# SCH_semi-automatic-healing-reminder_2026.net
KiCad netlist of a schematic drawn in EasyEDA
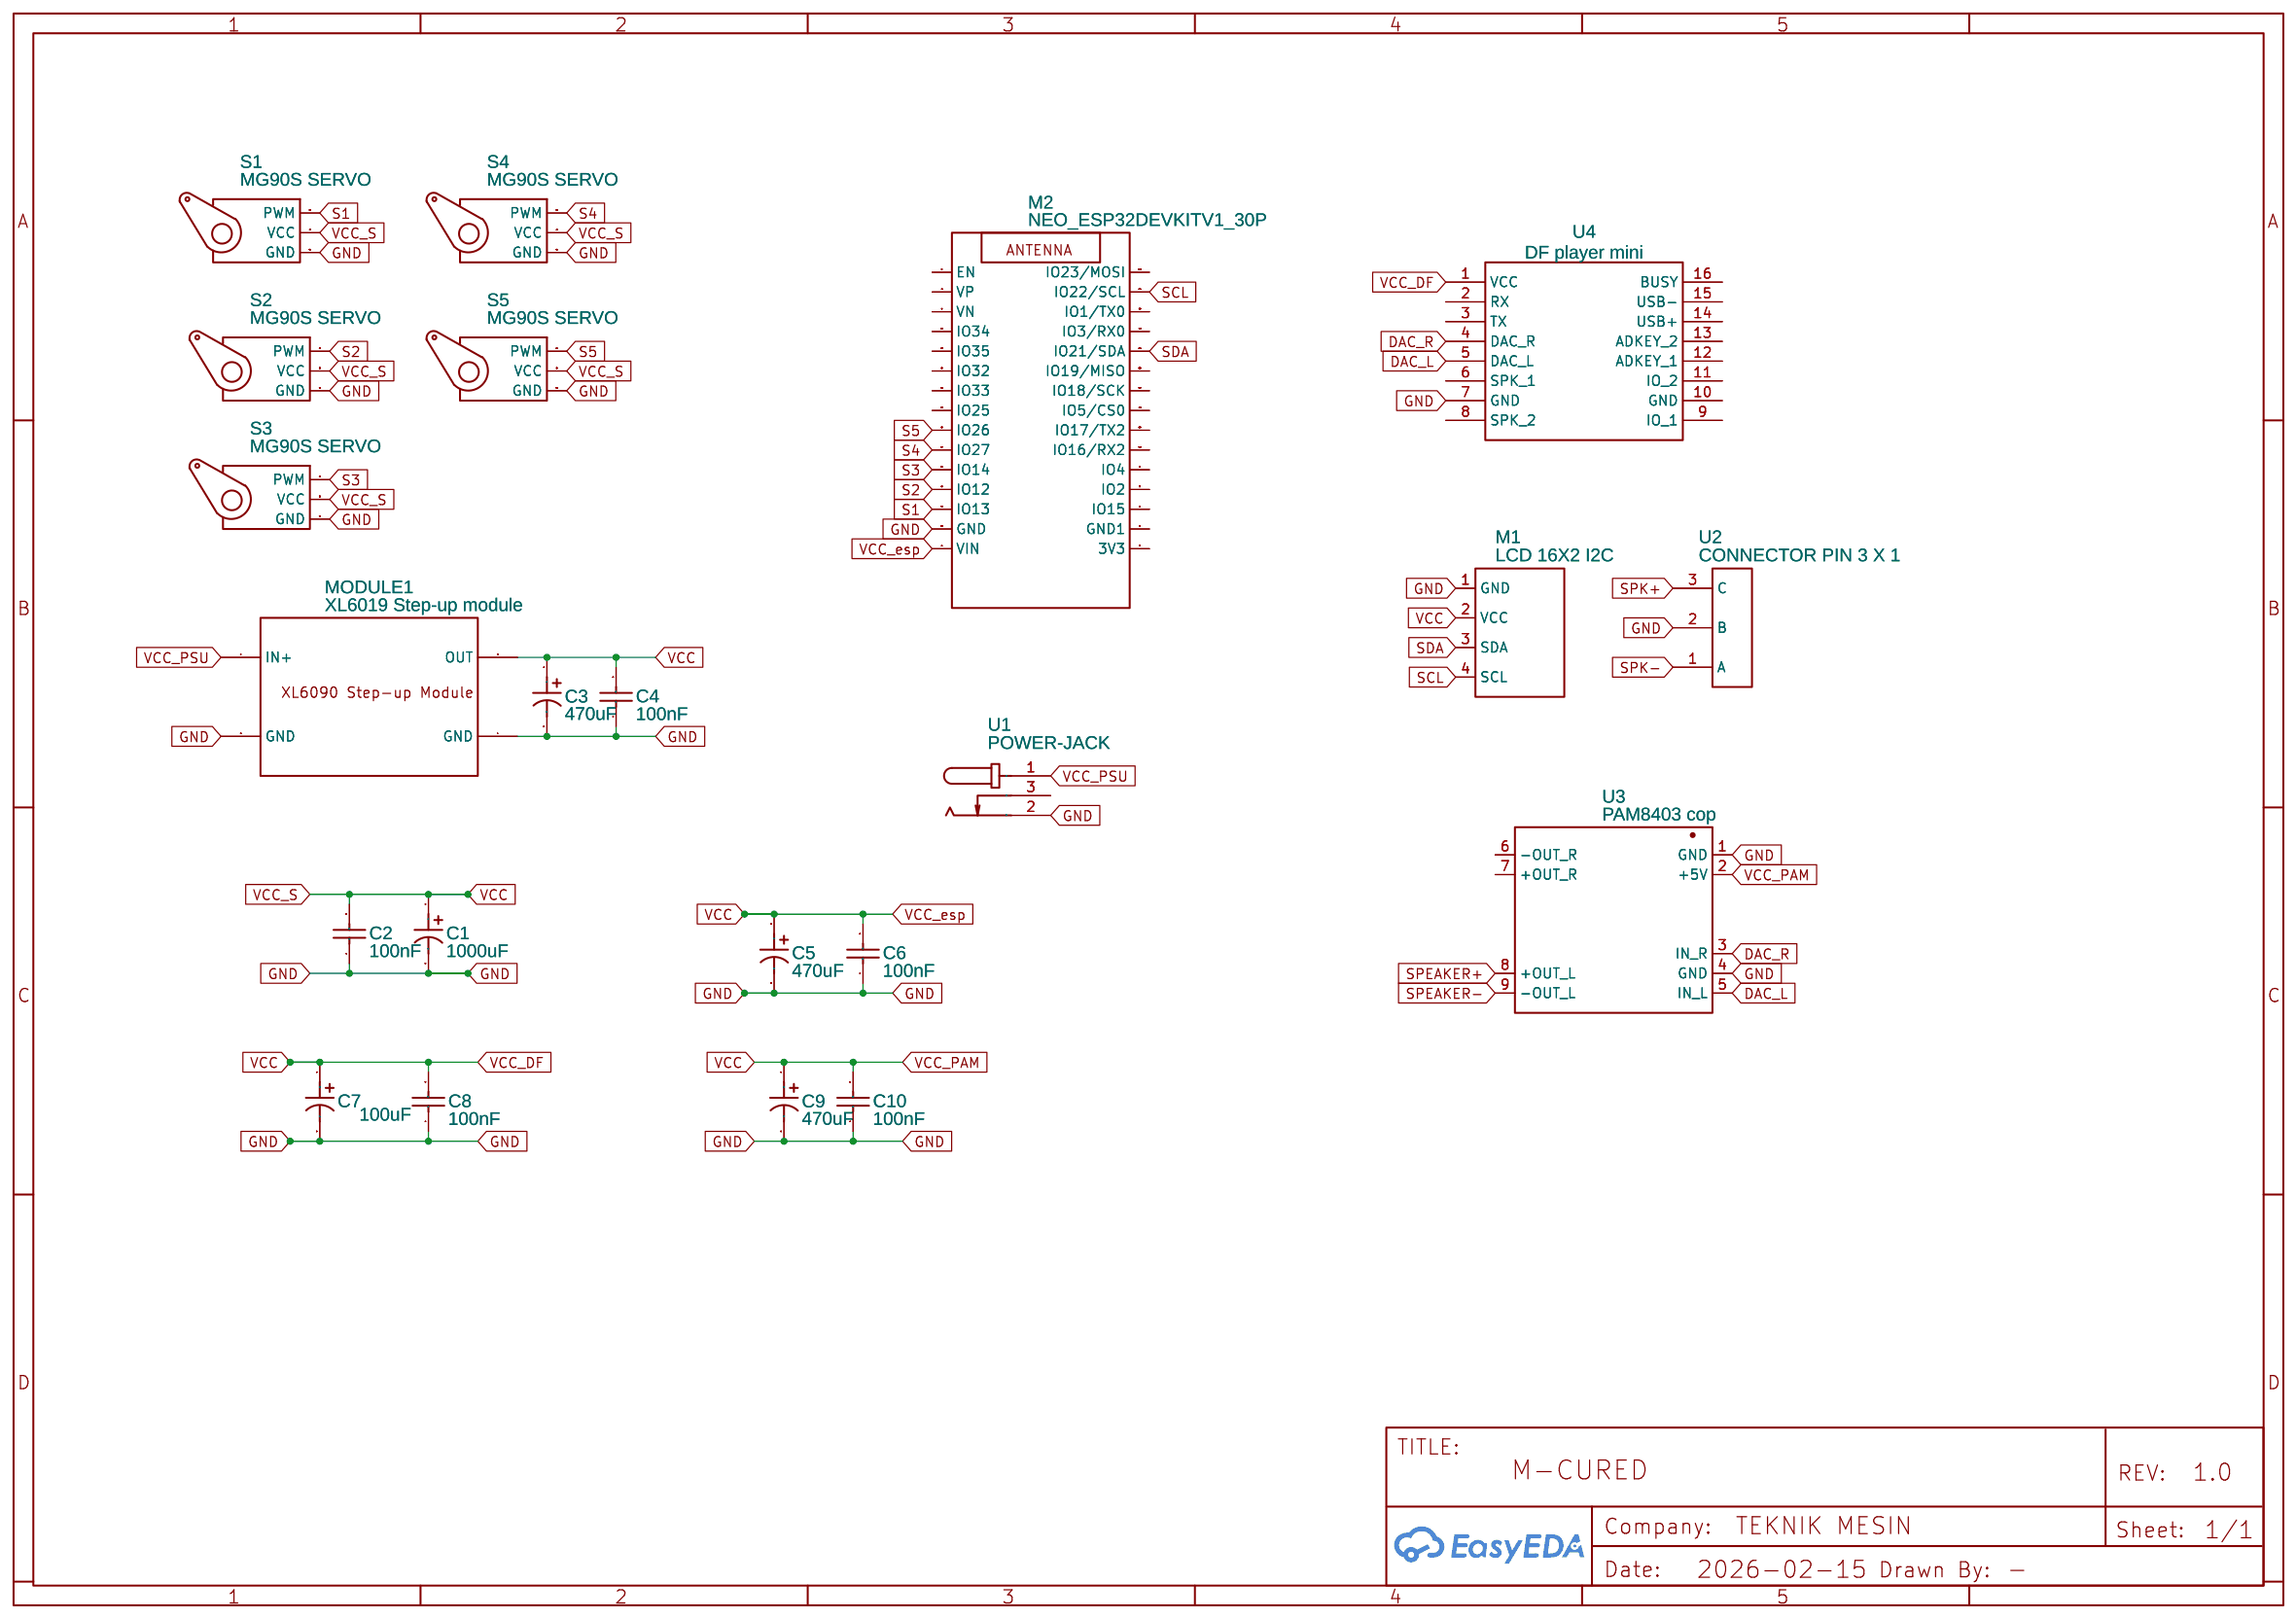
[diagram p0: schematic sheet]

(export (version "E")
  (design (tool "Eeschema 10.0.6"))
  (components
    (comp (ref "C1")
      (value "1000uF")
      (fields
        (field (name "Manufacturer Part") "1000uF10V8x14GF")
        (field (name "Manufacturer") "Econd(米朗电子)")
      )
      (libsource (lib "") (part "1000UF10V8X14GF"))
    )
    (comp (ref "C2")
      (value "100nF")
      (fields
        (field (name "Manufacturer Part") "100nF (104) ±20% 100V")
        (field (name "Manufacturer") "ReliaPro")
      )
      (libsource (lib "") (part "100nF"))
    )
    (comp (ref "C3")
      (value "470uF")
      (fields (field (name "Manufacturer Part") "470UF25VF140KM") (field (name "Manufacturer") "Econd(米朗电子)"))
      (libsource (lib "") (part "470UF25VF140KM"))
    )
    (comp (ref "C4")
      (value "100nF")
      (fields
        (field (name "Manufacturer Part") "100nF (104) ±20% 100V")
        (field (name "Manufacturer") "ReliaPro")
      )
      (libsource (lib "") (part "100nF"))
    )
    (comp (ref "C5")
      (value "470uF")
      (fields (field (name "Manufacturer Part") "470UF25VF140KM") (field (name "Manufacturer") "Econd(米朗电子)"))
      (libsource (lib "") (part "470UF25VF140KM"))
    )
    (comp (ref "C6")
      (value "100nF")
      (fields
        (field (name "Manufacturer Part") "100nF (104) ±20% 100V")
        (field (name "Manufacturer") "ReliaPro")
      )
      (libsource (lib "") (part "100nF"))
    )
    (comp (ref "C7")
      (value "100uF")
      (fields
        (field (name "Manufacturer Part") "100uF25V6.3x11KM")
        (field (name "Manufacturer") "Econd(米朗电子)")
      )
      (libsource (lib "") (part "100UF25V6.3X11KM"))
    )
    (comp (ref "C8")
      (value "100nF")
      (fields
        (field (name "Manufacturer Part") "100nF (104) ±20% 100V")
        (field (name "Manufacturer") "ReliaPro")
      )
      (libsource (lib "") (part "100nF"))
    )
    (comp (ref "C9")
      (value "470uF")
      (fields (field (name "Manufacturer Part") "470UF25VF140KM") (field (name "Manufacturer") "Econd(米朗电子)"))
      (libsource (lib "") (part "470UF25VF140KM"))
    )
    (comp (ref "C10")
      (value "100nF")
      (fields
        (field (name "Manufacturer Part") "100nF (104) ±20% 100V")
        (field (name "Manufacturer") "ReliaPro")
      )
      (libsource (lib "") (part "100nF"))
    )
    (comp (ref "M1") (value "LCD 16X2 I2C") (libsource (lib "") (part "LCD 16X2 I2C")))
    (comp (ref "M2") (value "NEO_ESP32DEVKITV1_30P") (libsource (lib "") (part "NEO_ESP32DEVKITV1_30P")))
    (comp (ref "MODULE1") (value "XL6019 Step-up module") (libsource (lib "") (part "XL6019 Step-up module")))
    (comp (ref "S1") (value "MG90S SERVO") (libsource (lib "") (part "MG90S SERVO")))
    (comp (ref "S2") (value "MG90S SERVO") (libsource (lib "") (part "MG90S SERVO")))
    (comp (ref "S3") (value "MG90S SERVO") (libsource (lib "") (part "MG90S SERVO")))
    (comp (ref "S4") (value "MG90S SERVO") (libsource (lib "") (part "MG90S SERVO")))
    (comp (ref "S5") (value "MG90S SERVO") (libsource (lib "") (part "MG90S SERVO")))
    (comp (ref "U1")
      (value "POWER-JACK")
      (fields (field (name "Manufacturer") "索峰"))
      (libsource (lib "") (part "POWER-JACK"))
    )
    (comp (ref "U2") (value "CONNECTOR PIN 3 X 1") (libsource (lib "") (part "CONNECTOR PIN 3 X 1")))
    (comp (ref "U3")
      (value "PAM8403 cop")
      (fields (field (name "Manufacturer Part") "PAM8403DR") (field (name "Manufacturer") "DIODES"))
      (libsource (lib "") (part "PAM8403 cop"))
    )
    (comp (ref "U4") (value "DF player mini") (libsource (lib "") (part "DF player mini")))
  )
  (nets
    (net (code "1") (name "DAC_L") (class "Default")
      (node (ref "U3") (pin "5") (pinfunction "IN_L_5") (pintype "unspecified"))
      (node (ref "U4") (pin "5") (pinfunction "DAC_L_5") (pintype "unspecified"))
    )
    (net (code "2") (name "DAC_R") (class "Default")
      (node (ref "U3") (pin "3") (pinfunction "IN_R_3") (pintype "unspecified"))
      (node (ref "U4") (pin "4") (pinfunction "DAC_R_4") (pintype "unspecified"))
    )
    (net (code "3") (name "GND") (class "Default")
      (node (ref "C1") (pin "2") (pinfunction "2_2") (pintype "input"))
      (node (ref "C10") (pin "1") (pinfunction "1_1") (pintype "unspecified"))
      (node (ref "C2") (pin "1") (pinfunction "1_1") (pintype "unspecified"))
      (node (ref "C3") (pin "2") (pinfunction "2_2") (pintype "input"))
      (node (ref "C4") (pin "1") (pinfunction "1_1") (pintype "unspecified"))
      (node (ref "C5") (pin "2") (pinfunction "2_2") (pintype "input"))
      (node (ref "C6") (pin "1") (pinfunction "1_1") (pintype "unspecified"))
      (node (ref "C7") (pin "2") (pinfunction "2_2") (pintype "input"))
      (node (ref "C8") (pin "1") (pinfunction "1_1") (pintype "unspecified"))
      (node (ref "C9") (pin "2") (pinfunction "2_2") (pintype "input"))
      (node (ref "M1") (pin "1") (pinfunction "GND_1") (pintype "unspecified"))
      (node (ref "M2") (pin "GND") (pinfunction "GND_GND") (pintype "bidirectional"))
      (node (ref "MODULE1") (pin "2") (pinfunction "GND_2") (pintype "unspecified"))
      (node (ref "MODULE1") (pin "4") (pinfunction "GND_4") (pintype "unspecified"))
      (node (ref "S1") (pin "GND") (pinfunction "GND_GND") (pintype "input"))
      (node (ref "S2") (pin "GND") (pinfunction "GND_GND") (pintype "input"))
      (node (ref "S3") (pin "GND") (pinfunction "GND_GND") (pintype "input"))
      (node (ref "S4") (pin "GND") (pinfunction "GND_GND") (pintype "input"))
      (node (ref "S5") (pin "GND") (pinfunction "GND_GND") (pintype "input"))
      (node (ref "U1") (pin "2") (pinfunction "2_2") (pintype "unspecified"))
      (node (ref "U2") (pin "2") (pinfunction "B_2") (pintype "unspecified"))
      (node (ref "U3") (pin "1") (pinfunction "GND_1") (pintype "unspecified"))
      (node (ref "U3") (pin "4") (pinfunction "GND_4") (pintype "unspecified"))
      (node (ref "U4") (pin "7") (pinfunction "GND_7") (pintype "unspecified"))
    )
    (net (code "4") (name "S1") (class "Default")
      (node (ref "M2") (pin "IO13") (pinfunction "IO13_IO13") (pintype "bidirectional"))
      (node (ref "S1") (pin "PWM") (pinfunction "PWM_PWM") (pintype "input"))
    )
    (net (code "5") (name "S2") (class "Default")
      (node (ref "M2") (pin "IO12") (pinfunction "IO12_IO12") (pintype "bidirectional"))
      (node (ref "S2") (pin "PWM") (pinfunction "PWM_PWM") (pintype "input"))
    )
    (net (code "6") (name "S3") (class "Default")
      (node (ref "M2") (pin "IO14") (pinfunction "IO14_IO14") (pintype "bidirectional"))
      (node (ref "S3") (pin "PWM") (pinfunction "PWM_PWM") (pintype "input"))
    )
    (net (code "7") (name "S4") (class "Default")
      (node (ref "M2") (pin "IO27") (pinfunction "IO27_IO27") (pintype "bidirectional"))
      (node (ref "S4") (pin "PWM") (pinfunction "PWM_PWM") (pintype "input"))
    )
    (net (code "8") (name "S5") (class "Default")
      (node (ref "M2") (pin "IO26") (pinfunction "IO26_IO26") (pintype "bidirectional"))
      (node (ref "S5") (pin "PWM") (pinfunction "PWM_PWM") (pintype "input"))
    )
    (net (code "9") (name "SCL") (class "Default")
      (node (ref "M1") (pin "4") (pinfunction "SCL_4") (pintype "unspecified"))
      (node (ref "M2") (pin "IO22/SCL") (pinfunction "IO22/SCL_IO22/SCL") (pintype "bidirectional"))
    )
    (net (code "10") (name "SDA") (class "Default")
      (node (ref "M1") (pin "3") (pinfunction "SDA_3") (pintype "unspecified"))
      (node (ref "M2") (pin "IO21/SDA") (pinfunction "IO21/SDA_IO21/SDA") (pintype "bidirectional"))
    )
    (net (code "11") (name "SPEAKER+") (class "Default")
      (node (ref "U3") (pin "8") (pinfunction "+OUT_L_8") (pintype "unspecified"))
    )
    (net (code "12") (name "SPEAKER-") (class "Default")
      (node (ref "U3") (pin "9") (pinfunction "-OUT_L_9") (pintype "unspecified"))
    )
    (net (code "13") (name "SPK+") (class "Default")
      (node (ref "U2") (pin "3") (pinfunction "C_3") (pintype "unspecified"))
    )
    (net (code "14") (name "SPK-") (class "Default")
      (node (ref "U2") (pin "1") (pinfunction "A_1") (pintype "unspecified"))
    )
    (net (code "15") (name "VCC") (class "Default")
      (node (ref "C1") (pin "1") (pinfunction "1_1") (pintype "input"))
      (node (ref "C10") (pin "2") (pinfunction "2_2") (pintype "unspecified"))
      (node (ref "C2") (pin "2") (pinfunction "2_2") (pintype "unspecified"))
      (node (ref "C3") (pin "1") (pinfunction "1_1") (pintype "input"))
      (node (ref "C4") (pin "2") (pinfunction "2_2") (pintype "unspecified"))
      (node (ref "C5") (pin "1") (pinfunction "1_1") (pintype "input"))
      (node (ref "C6") (pin "2") (pinfunction "2_2") (pintype "unspecified"))
      (node (ref "C7") (pin "1") (pinfunction "1_1") (pintype "input"))
      (node (ref "C8") (pin "2") (pinfunction "2_2") (pintype "unspecified"))
      (node (ref "C9") (pin "1") (pinfunction "1_1") (pintype "input"))
      (node (ref "M1") (pin "2") (pinfunction "VCC_2") (pintype "unspecified"))
      (node (ref "M2") (pin "VIN") (pinfunction "VIN_VIN") (pintype "bidirectional"))
      (node (ref "MODULE1") (pin "3") (pinfunction "OUT_3") (pintype "unspecified"))
      (node (ref "S1") (pin "VCC") (pinfunction "VCC_VCC") (pintype "input"))
      (node (ref "S2") (pin "VCC") (pinfunction "VCC_VCC") (pintype "input"))
      (node (ref "S3") (pin "VCC") (pinfunction "VCC_VCC") (pintype "input"))
      (node (ref "S4") (pin "VCC") (pinfunction "VCC_VCC") (pintype "input"))
      (node (ref "S5") (pin "VCC") (pinfunction "VCC_VCC") (pintype "input"))
      (node (ref "U3") (pin "2") (pinfunction "+5V_2") (pintype "unspecified"))
      (node (ref "U4") (pin "1") (pinfunction "VCC_1") (pintype "unspecified"))
    )
    (net (code "16") (name "VCC_PSU") (class "Default")
      (node (ref "MODULE1") (pin "1") (pinfunction "IN+_1") (pintype "unspecified"))
      (node (ref "U1") (pin "1") (pinfunction "1_1") (pintype "unspecified"))
    )
    (net (code "17") (name "unconnected-(M2-Pad3V3)") (class "Default")
      (node (ref "M2") (pin "3V3") (pinfunction "3V3_3V3") (pintype "bidirectional"))
    )
    (net (code "18") (name "unconnected-(M2-PadEN)") (class "Default")
      (node (ref "M2") (pin "EN") (pinfunction "EN_EN") (pintype "bidirectional"))
    )
    (net (code "19") (name "unconnected-(M2-PadGND1)") (class "Default")
      (node (ref "M2") (pin "GND1") (pinfunction "GND1_GND1") (pintype "bidirectional"))
    )
    (net (code "20") (name "unconnected-(M2-PadIO1{slash}TX0)") (class "Default")
      (node (ref "M2") (pin "IO1/TX0") (pinfunction "IO1/TX0_IO1/TX0") (pintype "bidirectional"))
    )
    (net (code "21") (name "unconnected-(M2-PadIO2)") (class "Default")
      (node (ref "M2") (pin "IO2") (pinfunction "IO2_IO2") (pintype "bidirectional"))
    )
    (net (code "22") (name "unconnected-(M2-PadIO3{slash}RX0)") (class "Default")
      (node (ref "M2") (pin "IO3/RX0") (pinfunction "IO3/RX0_IO3/RX0") (pintype "bidirectional"))
    )
    (net (code "23") (name "unconnected-(M2-PadIO4)") (class "Default")
      (node (ref "M2") (pin "IO4") (pinfunction "IO4_IO4") (pintype "bidirectional"))
    )
    (net (code "24") (name "unconnected-(M2-PadIO5{slash}CS0)") (class "Default")
      (node (ref "M2") (pin "IO5/CS0") (pinfunction "IO5/CS0_IO5/CS0") (pintype "bidirectional"))
    )
    (net (code "25") (name "unconnected-(M2-PadIO15)") (class "Default")
      (node (ref "M2") (pin "IO15") (pinfunction "IO15_IO15") (pintype "bidirectional"))
    )
    (net (code "26") (name "unconnected-(M2-PadIO16{slash}RX2)") (class "Default")
      (node (ref "M2") (pin "IO16/RX2") (pinfunction "IO16/RX2_IO16/RX2") (pintype "bidirectional"))
    )
    (net (code "27") (name "unconnected-(M2-PadIO17{slash}TX2)") (class "Default")
      (node (ref "M2") (pin "IO17/TX2") (pinfunction "IO17/TX2_IO17/TX2") (pintype "bidirectional"))
    )
    (net (code "28") (name "unconnected-(M2-PadIO18{slash}SCK)") (class "Default")
      (node (ref "M2") (pin "IO18/SCK") (pinfunction "IO18/SCK_IO18/SCK") (pintype "bidirectional"))
    )
    (net (code "29") (name "unconnected-(M2-PadIO19{slash}MISO)") (class "Default")
      (node (ref "M2") (pin "IO19/MISO") (pinfunction "IO19/MISO_IO19/MISO") (pintype "bidirectional"))
    )
    (net (code "30") (name "unconnected-(M2-PadIO23{slash}MOSI)") (class "Default")
      (node (ref "M2") (pin "IO23/MOSI") (pinfunction "IO23/MOSI_IO23/MOSI") (pintype "bidirectional"))
    )
    (net (code "31") (name "unconnected-(M2-PadIO25)") (class "Default")
      (node (ref "M2") (pin "IO25") (pinfunction "IO25_IO25") (pintype "bidirectional"))
    )
    (net (code "32") (name "unconnected-(M2-PadIO32)") (class "Default")
      (node (ref "M2") (pin "IO32") (pinfunction "IO32_IO32") (pintype "bidirectional"))
    )
    (net (code "33") (name "unconnected-(M2-PadIO33)") (class "Default")
      (node (ref "M2") (pin "IO33") (pinfunction "IO33_IO33") (pintype "bidirectional"))
    )
    (net (code "34") (name "unconnected-(M2-PadIO34)") (class "Default")
      (node (ref "M2") (pin "IO34") (pinfunction "IO34_IO34") (pintype "bidirectional"))
    )
    (net (code "35") (name "unconnected-(M2-PadIO35)") (class "Default")
      (node (ref "M2") (pin "IO35") (pinfunction "IO35_IO35") (pintype "bidirectional"))
    )
    (net (code "36") (name "unconnected-(M2-PadVN)") (class "Default")
      (node (ref "M2") (pin "VN") (pinfunction "VN_VN") (pintype "bidirectional"))
    )
    (net (code "37") (name "unconnected-(M2-PadVP)") (class "Default")
      (node (ref "M2") (pin "VP") (pinfunction "VP_VP") (pintype "bidirectional"))
    )
    (net (code "38") (name "unconnected-(U1-Pad3)") (class "Default")
      (node (ref "U1") (pin "3") (pinfunction "3_3") (pintype "unspecified"))
    )
    (net (code "39") (name "unconnected-(U3-+OUT_R-Pad7)") (class "Default")
      (node (ref "U3") (pin "7") (pinfunction "+OUT_R_7") (pintype "unspecified"))
    )
    (net (code "40") (name "unconnected-(U3--OUT_R-Pad6)") (class "Default")
      (node (ref "U3") (pin "6") (pinfunction "-OUT_R_6") (pintype "unspecified"))
    )
    (net (code "41") (name "unconnected-(U4-ADKEY_1-Pad12)") (class "Default")
      (node (ref "U4") (pin "12") (pinfunction "ADKEY_1_12") (pintype "unspecified"))
    )
    (net (code "42") (name "unconnected-(U4-ADKEY_2-Pad13)") (class "Default")
      (node (ref "U4") (pin "13") (pinfunction "ADKEY_2_13") (pintype "unspecified"))
    )
    (net (code "43") (name "unconnected-(U4-BUSY-Pad16)") (class "Default")
      (node (ref "U4") (pin "16") (pinfunction "BUSY_16") (pintype "unspecified"))
    )
    (net (code "44") (name "unconnected-(U4-GND-Pad10)") (class "Default")
      (node (ref "U4") (pin "10") (pinfunction "GND_10") (pintype "unspecified"))
    )
    (net (code "45") (name "unconnected-(U4-IO_1-Pad9)") (class "Default")
      (node (ref "U4") (pin "9") (pinfunction "IO_1_9") (pintype "unspecified"))
    )
    (net (code "46") (name "unconnected-(U4-IO_2-Pad11)") (class "Default")
      (node (ref "U4") (pin "11") (pinfunction "IO_2_11") (pintype "unspecified"))
    )
    (net (code "47") (name "unconnected-(U4-RX-Pad2)") (class "Default")
      (node (ref "U4") (pin "2") (pinfunction "RX_2") (pintype "unspecified"))
    )
    (net (code "48") (name "unconnected-(U4-SPK_1-Pad6)") (class "Default")
      (node (ref "U4") (pin "6") (pinfunction "SPK_1_6") (pintype "unspecified"))
    )
    (net (code "49") (name "unconnected-(U4-SPK_2-Pad8)") (class "Default")
      (node (ref "U4") (pin "8") (pinfunction "SPK_2_8") (pintype "unspecified"))
    )
    (net (code "50") (name "unconnected-(U4-TX-Pad3)") (class "Default")
      (node (ref "U4") (pin "3") (pinfunction "TX_3") (pintype "unspecified"))
    )
    (net (code "51") (name "unconnected-(U4-USB+-Pad14)") (class "Default")
      (node (ref "U4") (pin "14") (pinfunction "USB+_14") (pintype "unspecified"))
    )
    (net (code "52") (name "unconnected-(U4-USB--Pad15)") (class "Default")
      (node (ref "U4") (pin "15") (pinfunction "USB-_15") (pintype "unspecified"))
    )
  )
)
